# CYM1A113.net
KiCad netlist of a schematic drawn in EAGLE
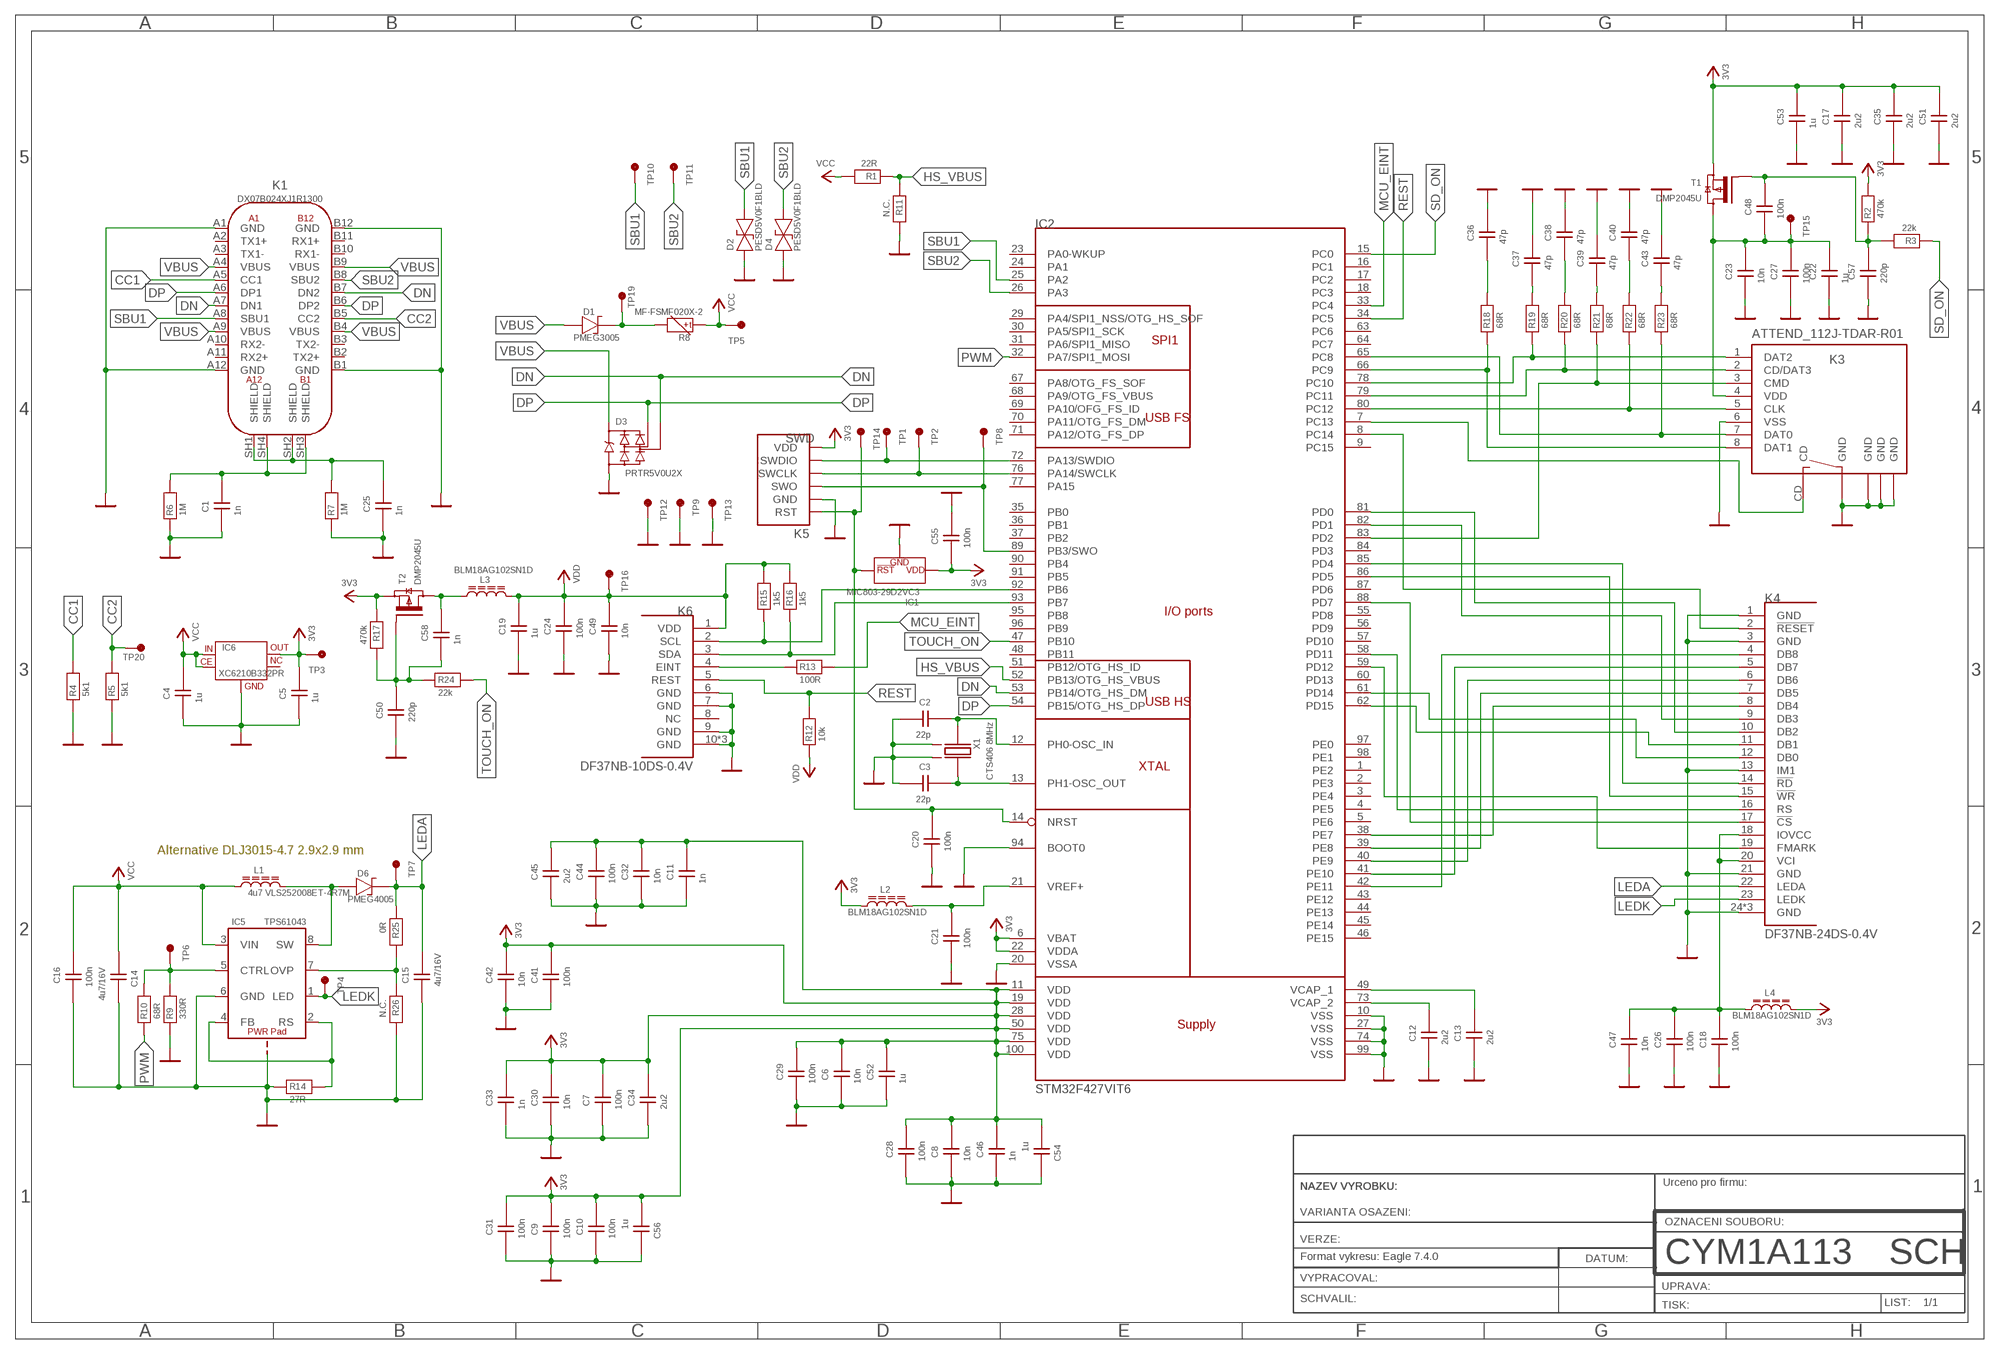
[diagram p0: schematic, sheet 1]

(export (version "E")
  (design (tool "Eeschema 10.0.6"))
  (components
    (comp (ref "C1")
      (value "1n")
      (footprint "eagle-import:0402")
      (libsource (lib "eagle-import") (part "C_0402"))
    )
    (comp (ref "C2")
      (value "22p")
      (footprint "eagle-import:0402")
      (libsource (lib "eagle-import") (part "C_0402"))
    )
    (comp (ref "C3")
      (value "22p")
      (footprint "eagle-import:0402")
      (libsource (lib "eagle-import") (part "C_0402"))
    )
    (comp (ref "C4")
      (value "1u")
      (footprint "eagle-import:0603_REFLOW")
      (libsource (lib "eagle-import") (part "C_0603$REFLOW"))
    )
    (comp (ref "C5")
      (value "1u")
      (footprint "eagle-import:0603")
      (libsource (lib "eagle-import") (part "C_0603"))
    )
    (comp (ref "C6")
      (value "10n")
      (footprint "eagle-import:0402")
      (libsource (lib "eagle-import") (part "C_0402"))
    )
    (comp (ref "C7")
      (value "100n")
      (footprint "eagle-import:0402")
      (libsource (lib "eagle-import") (part "C_0402"))
    )
    (comp (ref "C8")
      (value "10n")
      (footprint "eagle-import:0402")
      (libsource (lib "eagle-import") (part "C_0402"))
    )
    (comp (ref "C9")
      (value "100n")
      (footprint "eagle-import:0402")
      (libsource (lib "eagle-import") (part "C_0402"))
    )
    (comp (ref "C10")
      (value "100n")
      (footprint "eagle-import:0402")
      (libsource (lib "eagle-import") (part "C_0402"))
    )
    (comp (ref "C11")
      (value "1n")
      (footprint "eagle-import:0402")
      (libsource (lib "eagle-import") (part "C_0402"))
    )
    (comp (ref "C12")
      (value "2u2")
      (footprint "eagle-import:0805_REFLOW")
      (libsource (lib "eagle-import") (part "C_0805$REFLOW"))
    )
    (comp (ref "C13")
      (value "2u2")
      (footprint "eagle-import:0805_REFLOW")
      (libsource (lib "eagle-import") (part "C_0805$REFLOW"))
    )
    (comp (ref "C14")
      (value "4u7/16V")
      (footprint "eagle-import:0805_REFLOW")
      (libsource (lib "eagle-import") (part "C_0805$REFLOW"))
    )
    (comp (ref "C15")
      (value "4u7/16V")
      (footprint "eagle-import:0805_REFLOW")
      (libsource (lib "eagle-import") (part "C_0805$REFLOW"))
    )
    (comp (ref "C16")
      (value "100n")
      (footprint "eagle-import:0402")
      (libsource (lib "eagle-import") (part "C_0402"))
    )
    (comp (ref "C17")
      (value "2u2")
      (footprint "eagle-import:0805_REFLOW")
      (libsource (lib "eagle-import") (part "C_0805$REFLOW"))
    )
    (comp (ref "C18")
      (value "100n")
      (footprint "eagle-import:0402")
      (libsource (lib "eagle-import") (part "C_0402"))
    )
    (comp (ref "C19")
      (value "1u")
      (footprint "eagle-import:0603_REFLOW")
      (libsource (lib "eagle-import") (part "C_0603$REFLOW"))
    )
    (comp (ref "C20")
      (value "100n")
      (footprint "eagle-import:0402")
      (libsource (lib "eagle-import") (part "C_0402"))
    )
    (comp (ref "C21")
      (value "100n")
      (footprint "eagle-import:0402")
      (libsource (lib "eagle-import") (part "C_0402"))
    )
    (comp (ref "C22")
      (value "1u")
      (footprint "eagle-import:0603_REFLOW")
      (libsource (lib "eagle-import") (part "C_0603$REFLOW"))
    )
    (comp (ref "C23")
      (value "10n")
      (footprint "eagle-import:0402")
      (libsource (lib "eagle-import") (part "C_0402"))
    )
    (comp (ref "C24")
      (value "100n")
      (footprint "eagle-import:0402")
      (libsource (lib "eagle-import") (part "C_0402"))
    )
    (comp (ref "C25")
      (value "1n")
      (footprint "eagle-import:0402")
      (libsource (lib "eagle-import") (part "C_0402"))
    )
    (comp (ref "C26")
      (value "100n")
      (footprint "eagle-import:0402")
      (libsource (lib "eagle-import") (part "C_0402"))
    )
    (comp (ref "C27")
      (value "100n")
      (footprint "eagle-import:0402")
      (libsource (lib "eagle-import") (part "C_0402"))
    )
    (comp (ref "C28")
      (value "100n")
      (footprint "eagle-import:0402")
      (libsource (lib "eagle-import") (part "C_0402"))
    )
    (comp (ref "C29")
      (value "100n")
      (footprint "eagle-import:0402")
      (libsource (lib "eagle-import") (part "C_0402"))
    )
    (comp (ref "C30")
      (value "10n")
      (footprint "eagle-import:0402")
      (libsource (lib "eagle-import") (part "C_0402"))
    )
    (comp (ref "C31")
      (value "100n")
      (footprint "eagle-import:0402")
      (libsource (lib "eagle-import") (part "C_0402"))
    )
    (comp (ref "C32")
      (value "10n")
      (footprint "eagle-import:0402")
      (libsource (lib "eagle-import") (part "C_0402"))
    )
    (comp (ref "C33")
      (value "1n")
      (footprint "eagle-import:0402")
      (libsource (lib "eagle-import") (part "C_0402"))
    )
    (comp (ref "C34")
      (value "2u2")
      (footprint "eagle-import:0805_REFLOW")
      (libsource (lib "eagle-import") (part "C_0805$REFLOW"))
    )
    (comp (ref "C35")
      (value "2u2")
      (footprint "eagle-import:0805_REFLOW")
      (libsource (lib "eagle-import") (part "C_0805$REFLOW"))
    )
    (comp (ref "C36")
      (value "47p")
      (footprint "eagle-import:0402")
      (libsource (lib "eagle-import") (part "C_0402"))
    )
    (comp (ref "C37")
      (value "47p")
      (footprint "eagle-import:0402")
      (libsource (lib "eagle-import") (part "C_0402"))
    )
    (comp (ref "C38")
      (value "47p")
      (footprint "eagle-import:0402")
      (libsource (lib "eagle-import") (part "C_0402"))
    )
    (comp (ref "C39")
      (value "47p")
      (footprint "eagle-import:0402")
      (libsource (lib "eagle-import") (part "C_0402"))
    )
    (comp (ref "C40")
      (value "47p")
      (footprint "eagle-import:0402")
      (libsource (lib "eagle-import") (part "C_0402"))
    )
    (comp (ref "C41")
      (value "100n")
      (footprint "eagle-import:0402")
      (libsource (lib "eagle-import") (part "C_0402"))
    )
    (comp (ref "C42")
      (value "10n")
      (footprint "eagle-import:0402")
      (libsource (lib "eagle-import") (part "C_0402"))
    )
    (comp (ref "C43")
      (value "47p")
      (footprint "eagle-import:0402")
      (libsource (lib "eagle-import") (part "C_0402"))
    )
    (comp (ref "C44")
      (value "100n")
      (footprint "eagle-import:0402")
      (libsource (lib "eagle-import") (part "C_0402"))
    )
    (comp (ref "C45")
      (value "2u2")
      (footprint "eagle-import:0805_REFLOW")
      (libsource (lib "eagle-import") (part "C_0805$REFLOW"))
    )
    (comp (ref "C46")
      (value "1n")
      (footprint "eagle-import:0402")
      (libsource (lib "eagle-import") (part "C_0402"))
    )
    (comp (ref "C47")
      (value "10n")
      (footprint "eagle-import:0402")
      (libsource (lib "eagle-import") (part "C_0402"))
    )
    (comp (ref "C48")
      (value "100n")
      (footprint "eagle-import:0402")
      (libsource (lib "eagle-import") (part "C_0402"))
    )
    (comp (ref "C49")
      (value "10n")
      (footprint "eagle-import:0402")
      (libsource (lib "eagle-import") (part "C_0402"))
    )
    (comp (ref "C50")
      (value "220p")
      (footprint "eagle-import:0402")
      (libsource (lib "eagle-import") (part "C_0402"))
    )
    (comp (ref "C51")
      (value "2u2")
      (footprint "eagle-import:0805_REFLOW")
      (libsource (lib "eagle-import") (part "C_0805$REFLOW"))
    )
    (comp (ref "C52")
      (value "1u")
      (footprint "eagle-import:0603_REFLOW")
      (libsource (lib "eagle-import") (part "C_0603$REFLOW"))
    )
    (comp (ref "C53")
      (value "1u")
      (footprint "eagle-import:0603_REFLOW")
      (libsource (lib "eagle-import") (part "C_0603$REFLOW"))
    )
    (comp (ref "C54")
      (value "1u")
      (footprint "eagle-import:0603_REFLOW")
      (libsource (lib "eagle-import") (part "C_0603$REFLOW"))
    )
    (comp (ref "C55")
      (value "100n")
      (footprint "eagle-import:0402")
      (libsource (lib "eagle-import") (part "C_0402"))
    )
    (comp (ref "C56")
      (value "1u")
      (footprint "eagle-import:0603_REFLOW")
      (libsource (lib "eagle-import") (part "C_0603$REFLOW"))
    )
    (comp (ref "C57")
      (value "220p")
      (footprint "eagle-import:0402")
      (libsource (lib "eagle-import") (part "C_0402"))
    )
    (comp (ref "C58")
      (value "1n")
      (footprint "eagle-import:0402")
      (libsource (lib "eagle-import") (part "C_0402"))
    )
    (comp (ref "D1")
      (value "PMEG3005")
      (footprint "eagle-import:SOD323F")
      (libsource (lib "eagle-import") (part "DS_SOD323F"))
    )
    (comp (ref "D2")
      (value "PESD5V0F1BLD")
      (footprint "eagle-import:SOD882D")
      (libsource (lib "eagle-import") (part "D_TRANSIL_BI_SOD882D"))
    )
    (comp (ref "D3")
      (value "PRTR5V0U2X")
      (footprint "eagle-import:SOT143B_REFLOW")
      (libsource (lib "eagle-import") (part "PRTR5V0_SOT143B$REFLOW"))
    )
    (comp (ref "D4")
      (value "PESD5V0F1BLD")
      (footprint "eagle-import:SOD882D")
      (libsource (lib "eagle-import") (part "D_TRANSIL_BI_SOD882D"))
    )
    (comp (ref "D6")
      (value "PMEG4005")
      (footprint "eagle-import:SOD323F")
      (libsource (lib "eagle-import") (part "DS_SOD323F"))
    )
    (comp (ref "IC1")
      (value "MIC803-29D2VC3")
      (footprint "eagle-import:SOT23_MEDIUM_SIZE")
      (libsource (lib "eagle-import") (part "MIC803"))
    )
    (comp (ref "IC2")
      (value "STM32F427VIT6")
      (footprint "eagle-import:LQFP100_NO_CENTER_NO_TDOCU")
      (libsource (lib "eagle-import") (part "STM32F427_LQFP100"))
    )
    (comp (ref "IC5")
      (value "TPS61043")
      (footprint "eagle-import:WSON-8_3X3MM")
      (libsource (lib "eagle-import") (part "TP6104X_WSON-8_3X3MM"))
    )
    (comp (ref "IC6")
      (value "XC6210B332PR")
      (footprint "eagle-import:SOT89-5")
      (libsource (lib "eagle-import") (part "XC6210B_SOT89-5"))
    )
    (comp (ref "K1")
      (value "DX07B024XJ1R1300")
      (footprint "eagle-import:USB_C_JAE_DX07B024XJ1")
      (libsource (lib "eagle-import") (part "USB-C_JAE_DX07B024XJ1"))
    )
    (comp (ref "K3")
      (value "ATTEND_112J-TDAR-R01")
      (footprint "eagle-import:ATTEND_112J-TXAR-R01_SMALL")
      (libsource (lib "eagle-import") (part "KON_µSD_CARD_ATTEND_112J_TXAR_R01_SMALL"))
    )
    (comp (ref "K4")
      (value "DF37NB-24DS-0.4V")
      (footprint "eagle-import:DF37NB-24DS-0.4V")
      (libsource (lib "eagle-import") (part "DISPLEJ_154A2411CTP01"))
    )
    (comp (ref "K5")
      (value "SWD")
      (footprint "eagle-import:SWD")
      (libsource (lib "eagle-import") (part "SWD"))
    )
    (comp (ref "K6")
      (value "DF37NB-10DS-0.4V")
      (footprint "eagle-import:DF37NB-10DS-0.4V")
      (libsource (lib "eagle-import") (part "DISPLEJ_154A2411CTP01_TOUCH"))
    )
    (comp (ref "L1")
      (value "4u7 VLS252008ET-4R7M")
      (footprint "eagle-import:L_2.5X2.0")
      (libsource (lib "eagle-import") (part "L_2.5X2.0"))
    )
    (comp (ref "L2")
      (value "BLM18AG102SN1D")
      (footprint "eagle-import:0603_REFLOW")
      (libsource (lib "eagle-import") (part "L_0603$REFLOW"))
    )
    (comp (ref "L3")
      (value "BLM18AG102SN1D")
      (footprint "eagle-import:0603_REFLOW")
      (libsource (lib "eagle-import") (part "L_0603$REFLOW"))
    )
    (comp (ref "L4")
      (value "BLM18AG102SN1D")
      (footprint "eagle-import:0603_REFLOW")
      (libsource (lib "eagle-import") (part "L_0603$REFLOW"))
    )
    (comp (ref "R1")
      (value "22R")
      (footprint "eagle-import:0402")
      (libsource (lib "eagle-import") (part "R_0402"))
    )
    (comp (ref "R2")
      (value "470k")
      (footprint "eagle-import:0402")
      (libsource (lib "eagle-import") (part "R_0402"))
    )
    (comp (ref "R3")
      (value "22k")
      (footprint "eagle-import:0402")
      (libsource (lib "eagle-import") (part "R_0402"))
    )
    (comp (ref "R4")
      (value "5k1")
      (footprint "eagle-import:0402")
      (libsource (lib "eagle-import") (part "R_0402"))
    )
    (comp (ref "R5")
      (value "5k1")
      (footprint "eagle-import:0402")
      (libsource (lib "eagle-import") (part "R_0402"))
    )
    (comp (ref "R6")
      (value "1M")
      (footprint "eagle-import:0402")
      (libsource (lib "eagle-import") (part "R_0402"))
    )
    (comp (ref "R7")
      (value "1M")
      (footprint "eagle-import:0402")
      (libsource (lib "eagle-import") (part "R_0402"))
    )
    (comp (ref "R8")
      (value "MF-FSMF020X-2")
      (footprint "eagle-import:0603")
      (libsource (lib "eagle-import") (part "POLYSWITCH_0603"))
    )
    (comp (ref "R9")
      (value "330R")
      (footprint "eagle-import:0402")
      (libsource (lib "eagle-import") (part "R_0402"))
    )
    (comp (ref "R10")
      (value "68R")
      (footprint "eagle-import:0402")
      (libsource (lib "eagle-import") (part "R_0402"))
    )
    (comp (ref "R11")
      (value "N.C.")
      (footprint "eagle-import:0402")
      (libsource (lib "eagle-import") (part "R_0402"))
    )
    (comp (ref "R12")
      (value "10k")
      (footprint "eagle-import:0402")
      (libsource (lib "eagle-import") (part "R_0402"))
    )
    (comp (ref "R13")
      (value "100R")
      (footprint "eagle-import:0402")
      (libsource (lib "eagle-import") (part "R_0402"))
    )
    (comp (ref "R14")
      (value "27R")
      (footprint "eagle-import:0402")
      (libsource (lib "eagle-import") (part "R_0402"))
    )
    (comp (ref "R15")
      (value "1k5")
      (footprint "eagle-import:0402")
      (libsource (lib "eagle-import") (part "R_0402"))
    )
    (comp (ref "R16")
      (value "1k5")
      (footprint "eagle-import:0402")
      (libsource (lib "eagle-import") (part "R_0402"))
    )
    (comp (ref "R17")
      (value "470k")
      (footprint "eagle-import:0402")
      (libsource (lib "eagle-import") (part "R_0402"))
    )
    (comp (ref "R18")
      (value "68R")
      (footprint "eagle-import:0402")
      (libsource (lib "eagle-import") (part "R_0402"))
    )
    (comp (ref "R19")
      (value "68R")
      (footprint "eagle-import:0402")
      (libsource (lib "eagle-import") (part "R_0402"))
    )
    (comp (ref "R20")
      (value "68R")
      (footprint "eagle-import:0402")
      (libsource (lib "eagle-import") (part "R_0402"))
    )
    (comp (ref "R21")
      (value "68R")
      (footprint "eagle-import:0402")
      (libsource (lib "eagle-import") (part "R_0402"))
    )
    (comp (ref "R22")
      (value "68R")
      (footprint "eagle-import:0402")
      (libsource (lib "eagle-import") (part "R_0402"))
    )
    (comp (ref "R23")
      (value "68R")
      (footprint "eagle-import:0402")
      (libsource (lib "eagle-import") (part "R_0402"))
    )
    (comp (ref "R24")
      (value "22k")
      (footprint "eagle-import:0402")
      (libsource (lib "eagle-import") (part "R_0402"))
    )
    (comp (ref "R25")
      (value "0R")
      (footprint "eagle-import:0402")
      (libsource (lib "eagle-import") (part "R_0402"))
    )
    (comp (ref "R26")
      (value "N.C.")
      (footprint "eagle-import:0402")
      (libsource (lib "eagle-import") (part "R_0402"))
    )
    (comp (ref "T1")
      (value "DMP2045U")
      (footprint "eagle-import:SOT23_REFLOW")
      (libsource (lib "eagle-import") (part "PMOS_SOT-23_REF"))
    )
    (comp (ref "T2")
      (value "DMP2045U")
      (footprint "eagle-import:SOT23_REFLOW")
      (libsource (lib "eagle-import") (part "PMOS_SOT-23_REF"))
    )
    (comp (ref "TP1")
      (value "MB_1.27")
      (footprint "eagle-import:MB1.27")
      (libsource (lib "eagle-import") (part "MB_1.27"))
    )
    (comp (ref "TP2")
      (value "MB_1.27")
      (footprint "eagle-import:MB1.27")
      (libsource (lib "eagle-import") (part "MB_1.27"))
    )
    (comp (ref "TP3")
      (value "MB_1.50")
      (footprint "eagle-import:MB1.5")
      (libsource (lib "eagle-import") (part "MB_1.50"))
    )
    (comp (ref "TP4")
      (value "MB_1.27")
      (footprint "eagle-import:MB1.27")
      (libsource (lib "eagle-import") (part "MB_1.27"))
    )
    (comp (ref "TP5")
      (value "MB_1.50")
      (footprint "eagle-import:MB1.5")
      (libsource (lib "eagle-import") (part "MB_1.50"))
    )
    (comp (ref "TP6")
      (value "MB_1.27")
      (footprint "eagle-import:MB1.27")
      (libsource (lib "eagle-import") (part "MB_1.27"))
    )
    (comp (ref "TP7")
      (value "MB_1.27")
      (footprint "eagle-import:MB1.27")
      (libsource (lib "eagle-import") (part "MB_1.27"))
    )
    (comp (ref "TP8")
      (value "MB_1.27")
      (footprint "eagle-import:MB1.27")
      (libsource (lib "eagle-import") (part "MB_1.27"))
    )
    (comp (ref "TP9")
      (value "MB_1.27")
      (footprint "eagle-import:MB1.27")
      (libsource (lib "eagle-import") (part "MB_1.27"))
    )
    (comp (ref "TP10")
      (value "MB_1.50")
      (footprint "eagle-import:MB1.5")
      (libsource (lib "eagle-import") (part "MB_1.50"))
    )
    (comp (ref "TP11")
      (value "MB_1.50")
      (footprint "eagle-import:MB1.5")
      (libsource (lib "eagle-import") (part "MB_1.50"))
    )
    (comp (ref "TP12")
      (value "MB_1.27")
      (footprint "eagle-import:MB1.27")
      (libsource (lib "eagle-import") (part "MB_1.27"))
    )
    (comp (ref "TP13")
      (value "MB_1.27")
      (footprint "eagle-import:MB1.27")
      (libsource (lib "eagle-import") (part "MB_1.27"))
    )
    (comp (ref "TP14")
      (value "MB_1.27")
      (footprint "eagle-import:MB1.27")
      (libsource (lib "eagle-import") (part "MB_1.27"))
    )
    (comp (ref "TP15")
      (value "MB_1.27")
      (footprint "eagle-import:MB1.27")
      (libsource (lib "eagle-import") (part "MB_1.27"))
    )
    (comp (ref "TP16")
      (value "MB_1.27")
      (footprint "eagle-import:MB1.27")
      (libsource (lib "eagle-import") (part "MB_1.27"))
    )
    (comp (ref "TP19")
      (value "MB_1.00")
      (footprint "eagle-import:MB_1.00")
      (libsource (lib "eagle-import") (part "MB_1.00"))
    )
    (comp (ref "TP20")
      (value "MB_1.00")
      (footprint "eagle-import:MB_1.00")
      (libsource (lib "eagle-import") (part "MB_1.00"))
    )
    (comp (ref "X1")
      (value "CTS406 8MHz")
      (footprint "eagle-import:X6,0X3,5")
      (libsource (lib "eagle-import") (part "X_4V_6,0X3,5"))
    )
  )
  (nets
    (net (code "1") (name "3V3") (class "Default")
      (node (ref "C10") (pin "P$2") (pinfunction "2_P$2") (pintype "passive"))
      (node (ref "C11") (pin "P$2") (pinfunction "2_P$2") (pintype "passive"))
      (node (ref "C17") (pin "2") (pinfunction "2_2") (pintype "passive"))
      (node (ref "C28") (pin "P$2") (pinfunction "2_P$2") (pintype "passive"))
      (node (ref "C29") (pin "P$2") (pinfunction "2_P$2") (pintype "passive"))
      (node (ref "C30") (pin "P$2") (pinfunction "2_P$2") (pintype "passive"))
      (node (ref "C31") (pin "P$2") (pinfunction "2_P$2") (pintype "passive"))
      (node (ref "C32") (pin "P$2") (pinfunction "2_P$2") (pintype "passive"))
      (node (ref "C33") (pin "P$2") (pinfunction "2_P$2") (pintype "passive"))
      (node (ref "C34") (pin "2") (pinfunction "2_2") (pintype "passive"))
      (node (ref "C35") (pin "2") (pinfunction "2_2") (pintype "passive"))
      (node (ref "C41") (pin "P$2") (pinfunction "2_P$2") (pintype "passive"))
      (node (ref "C42") (pin "P$2") (pinfunction "2_P$2") (pintype "passive"))
      (node (ref "C44") (pin "P$2") (pinfunction "2_P$2") (pintype "passive"))
      (node (ref "C45") (pin "2") (pinfunction "2_2") (pintype "passive"))
      (node (ref "C46") (pin "P$2") (pinfunction "2_P$2") (pintype "passive"))
      (node (ref "C5") (pin "2") (pinfunction "2_2") (pintype "passive"))
      (node (ref "C51") (pin "2") (pinfunction "2_2") (pintype "passive"))
      (node (ref "C52") (pin "2") (pinfunction "2_2") (pintype "passive"))
      (node (ref "C53") (pin "2") (pinfunction "2_2") (pintype "passive"))
      (node (ref "C54") (pin "1") (pinfunction "1_1") (pintype "passive"))
      (node (ref "C55") (pin "P$1") (pinfunction "1_P$1") (pintype "passive"))
      (node (ref "C56") (pin "1") (pinfunction "1_1") (pintype "passive"))
      (node (ref "C6") (pin "P$2") (pinfunction "2_P$2") (pintype "passive"))
      (node (ref "C7") (pin "P$2") (pinfunction "2_P$2") (pintype "passive"))
      (node (ref "C8") (pin "P$2") (pinfunction "2_P$2") (pintype "passive"))
      (node (ref "C9") (pin "P$2") (pinfunction "2_P$2") (pintype "passive"))
      (node (ref "IC1") (pin "3") (pinfunction "VDD_3") (pintype "passive"))
      (node (ref "IC2") (pin "100") (pinfunction "VDD_100") (pintype "power_in"))
      (node (ref "IC2") (pin "11") (pinfunction "VDD_11") (pintype "power_in"))
      (node (ref "IC2") (pin "19") (pinfunction "VDD_19") (pintype "power_in"))
      (node (ref "IC2") (pin "22") (pinfunction "VDDA_22") (pintype "power_in"))
      (node (ref "IC2") (pin "28") (pinfunction "VDD_28") (pintype "power_in"))
      (node (ref "IC2") (pin "50") (pinfunction "VDD_50") (pintype "power_in"))
      (node (ref "IC2") (pin "6") (pinfunction "VBAT_6") (pintype "power_in"))
      (node (ref "IC2") (pin "75") (pinfunction "VDD_75") (pintype "power_in"))
      (node (ref "IC6") (pin "5") (pinfunction "OUT_5") (pintype "passive"))
      (node (ref "K5") (pin "VCC") (pinfunction "VDD_VCC") (pintype "passive"))
      (node (ref "L2") (pin "1") (pinfunction "1_1") (pintype "passive"))
      (node (ref "L4") (pin "2") (pinfunction "2_2") (pintype "passive"))
      (node (ref "R17") (pin "P$1") (pinfunction "1_P$1") (pintype "passive"))
      (node (ref "R2") (pin "P$2") (pinfunction "2_P$2") (pintype "passive"))
      (node (ref "T1") (pin "1") (pinfunction "S_1") (pintype "passive"))
      (node (ref "T2") (pin "1") (pinfunction "S_1") (pintype "passive"))
      (node (ref "TP3") (pin "1") (pinfunction "1_1") (pintype "passive"))
    )
    (net (code "2") (name "CC1") (class "Default")
      (node (ref "K1") (pin "A5") (pinfunction "CC1_A5") (pintype "passive"))
      (node (ref "R4") (pin "P$2") (pinfunction "2_P$2") (pintype "passive"))
    )
    (net (code "3") (name "CC2") (class "Default")
      (node (ref "K1") (pin "B5") (pinfunction "CC2_B5") (pintype "passive"))
      (node (ref "R5") (pin "P$2") (pinfunction "2_P$2") (pintype "passive"))
      (node (ref "TP20") (pin "1") (pinfunction "1_1") (pintype "passive"))
    )
    (net (code "4") (name "DN") (class "Default")
      (node (ref "D3") (pin "3") (pinfunction "I/O2_3") (pintype "passive"))
      (node (ref "IC2") (pin "53") (pinfunction "PB14/OTG_HS_DM_53") (pintype "bidirectional"))
      (node (ref "K1") (pin "A7") (pinfunction "DN1_A7") (pintype "passive"))
      (node (ref "K1") (pin "B7") (pinfunction "DN2_B7") (pintype "passive"))
    )
    (net (code "5") (name "DP") (class "Default")
      (node (ref "D3") (pin "2") (pinfunction "I/O1_2") (pintype "passive"))
      (node (ref "IC2") (pin "54") (pinfunction "PB15/OTG_HS_DP_54") (pintype "bidirectional"))
      (node (ref "K1") (pin "A6") (pinfunction "DP1_A6") (pintype "passive"))
      (node (ref "K1") (pin "B6") (pinfunction "DP2_B6") (pintype "passive"))
    )
    (net (code "6") (name "GND") (class "Default")
      (node (ref "C1") (pin "P$1") (pinfunction "1_P$1") (pintype "passive"))
      (node (ref "C10") (pin "P$1") (pinfunction "1_P$1") (pintype "passive"))
      (node (ref "C11") (pin "P$1") (pinfunction "1_P$1") (pintype "passive"))
      (node (ref "C12") (pin "1") (pinfunction "1_1") (pintype "passive"))
      (node (ref "C13") (pin "1") (pinfunction "1_1") (pintype "passive"))
      (node (ref "C14") (pin "2") (pinfunction "2_2") (pintype "passive"))
      (node (ref "C15") (pin "1") (pinfunction "1_1") (pintype "passive"))
      (node (ref "C16") (pin "P$1") (pinfunction "1_P$1") (pintype "passive"))
      (node (ref "C17") (pin "1") (pinfunction "1_1") (pintype "passive"))
      (node (ref "C18") (pin "P$1") (pinfunction "1_P$1") (pintype "passive"))
      (node (ref "C19") (pin "1") (pinfunction "1_1") (pintype "passive"))
      (node (ref "C2") (pin "P$1") (pinfunction "1_P$1") (pintype "passive"))
      (node (ref "C20") (pin "P$1") (pinfunction "1_P$1") (pintype "passive"))
      (node (ref "C21") (pin "P$1") (pinfunction "1_P$1") (pintype "passive"))
      (node (ref "C22") (pin "1") (pinfunction "1_1") (pintype "passive"))
      (node (ref "C23") (pin "P$1") (pinfunction "1_P$1") (pintype "passive"))
      (node (ref "C24") (pin "P$1") (pinfunction "1_P$1") (pintype "passive"))
      (node (ref "C25") (pin "P$1") (pinfunction "1_P$1") (pintype "passive"))
      (node (ref "C26") (pin "P$1") (pinfunction "1_P$1") (pintype "passive"))
      (node (ref "C27") (pin "P$1") (pinfunction "1_P$1") (pintype "passive"))
      (node (ref "C28") (pin "P$1") (pinfunction "1_P$1") (pintype "passive"))
      (node (ref "C29") (pin "P$1") (pinfunction "1_P$1") (pintype "passive"))
      (node (ref "C3") (pin "P$1") (pinfunction "1_P$1") (pintype "passive"))
      (node (ref "C30") (pin "P$1") (pinfunction "1_P$1") (pintype "passive"))
      (node (ref "C31") (pin "P$1") (pinfunction "1_P$1") (pintype "passive"))
      (node (ref "C32") (pin "P$1") (pinfunction "1_P$1") (pintype "passive"))
      (node (ref "C33") (pin "P$1") (pinfunction "1_P$1") (pintype "passive"))
      (node (ref "C34") (pin "1") (pinfunction "1_1") (pintype "passive"))
      (node (ref "C35") (pin "1") (pinfunction "1_1") (pintype "passive"))
      (node (ref "C36") (pin "P$2") (pinfunction "2_P$2") (pintype "passive"))
      (node (ref "C37") (pin "P$2") (pinfunction "2_P$2") (pintype "passive"))
      (node (ref "C38") (pin "P$2") (pinfunction "2_P$2") (pintype "passive"))
      (node (ref "C39") (pin "P$2") (pinfunction "2_P$2") (pintype "passive"))
      (node (ref "C4") (pin "1") (pinfunction "1_1") (pintype "passive"))
      (node (ref "C40") (pin "P$2") (pinfunction "2_P$2") (pintype "passive"))
      (node (ref "C41") (pin "P$1") (pinfunction "1_P$1") (pintype "passive"))
      (node (ref "C42") (pin "P$1") (pinfunction "1_P$1") (pintype "passive"))
      (node (ref "C43") (pin "P$2") (pinfunction "2_P$2") (pintype "passive"))
      (node (ref "C44") (pin "P$1") (pinfunction "1_P$1") (pintype "passive"))
      (node (ref "C45") (pin "1") (pinfunction "1_1") (pintype "passive"))
      (node (ref "C46") (pin "P$1") (pinfunction "1_P$1") (pintype "passive"))
      (node (ref "C47") (pin "P$1") (pinfunction "1_P$1") (pintype "passive"))
      (node (ref "C49") (pin "P$1") (pinfunction "1_P$1") (pintype "passive"))
      (node (ref "C5") (pin "1") (pinfunction "1_1") (pintype "passive"))
      (node (ref "C50") (pin "P$1") (pinfunction "1_P$1") (pintype "passive"))
      (node (ref "C51") (pin "1") (pinfunction "1_1") (pintype "passive"))
      (node (ref "C52") (pin "1") (pinfunction "1_1") (pintype "passive"))
      (node (ref "C53") (pin "1") (pinfunction "1_1") (pintype "passive"))
      (node (ref "C54") (pin "2") (pinfunction "2_2") (pintype "passive"))
      (node (ref "C55") (pin "P$2") (pinfunction "2_P$2") (pintype "passive"))
      (node (ref "C56") (pin "2") (pinfunction "2_2") (pintype "passive"))
      (node (ref "C57") (pin "P$1") (pinfunction "1_P$1") (pintype "passive"))
      (node (ref "C6") (pin "P$1") (pinfunction "1_P$1") (pintype "passive"))
      (node (ref "C7") (pin "P$1") (pinfunction "1_P$1") (pintype "passive"))
      (node (ref "C8") (pin "P$1") (pinfunction "1_P$1") (pintype "passive"))
      (node (ref "C9") (pin "P$1") (pinfunction "1_P$1") (pintype "passive"))
      (node (ref "D2") (pin "1") (pinfunction "1_1") (pintype "passive"))
      (node (ref "D3") (pin "1") (pinfunction "GND_1") (pintype "passive"))
      (node (ref "D4") (pin "1") (pinfunction "1_1") (pintype "passive"))
      (node (ref "IC1") (pin "1") (pinfunction "GND_1") (pintype "passive"))
      (node (ref "IC2") (pin "10") (pinfunction "VSS_10") (pintype "power_in"))
      (node (ref "IC2") (pin "20") (pinfunction "VSSA_20") (pintype "power_in"))
      (node (ref "IC2") (pin "27") (pinfunction "VSS_27") (pintype "power_in"))
      (node (ref "IC2") (pin "74") (pinfunction "VSS_74") (pintype "power_in"))
      (node (ref "IC2") (pin "94") (pinfunction "BOOT0_94") (pintype "input"))
      (node (ref "IC2") (pin "99") (pinfunction "VSS_99") (pintype "power_in"))
      (node (ref "IC5") (pin "6") (pinfunction "GND_6") (pintype "power_in"))
      (node (ref "IC5") (pin "EP") (pinfunction "EP_EP") (pintype "passive"))
      (node (ref "IC5") (pin "EP$1") (pinfunction "EP_EP$1") (pintype "passive"))
      (node (ref "IC5") (pin "EP$2") (pinfunction "EP_EP$2") (pintype "passive"))
      (node (ref "IC5") (pin "EP$3") (pinfunction "EP_EP$3") (pintype "passive"))
      (node (ref "IC5") (pin "EP$4") (pinfunction "EP_EP$4") (pintype "passive"))
      (node (ref "IC6") (pin "2") (pinfunction "GND_2") (pintype "passive"))
      (node (ref "K1") (pin "A1") (pinfunction "GND_A1") (pintype "passive"))
      (node (ref "K1") (pin "A12") (pinfunction "GND_A12") (pintype "passive"))
      (node (ref "K1") (pin "B1") (pinfunction "GND_B1") (pintype "passive"))
      (node (ref "K1") (pin "B12") (pinfunction "GND_B12") (pintype "passive"))
      (node (ref "K3") (pin "6") (pinfunction "VSS_6") (pintype "bidirectional"))
      (node (ref "K3") (pin "GND@1") (pinfunction "GND_GND@1") (pintype "power_in"))
      (node (ref "K3") (pin "GND@2") (pinfunction "GND_GND@2") (pintype "power_in"))
      (node (ref "K3") (pin "GND@3") (pinfunction "GND_GND@3") (pintype "power_in"))
      (node (ref "K3") (pin "GND@4") (pinfunction "GND_GND@4") (pintype "power_in"))
      (node (ref "K4") (pin "1") (pinfunction "GND_1") (pintype "power_in"))
      (node (ref "K4") (pin "13") (pinfunction "IM1_13") (pintype "bidirectional"))
      (node (ref "K4") (pin "21") (pinfunction "GND_21") (pintype "power_in"))
      (node (ref "K4") (pin "24") (pinfunction "GND_24") (pintype "power_in"))
      (node (ref "K4") (pin "25") (pinfunction "GND_25") (pintype "power_in"))
      (node (ref "K4") (pin "26") (pinfunction "GND_26") (pintype "power_in"))
      (node (ref "K4") (pin "3") (pinfunction "GND_3") (pintype "power_in"))
      (node (ref "K5") (pin "GND") (pinfunction "GND_GND") (pintype "passive"))
      (node (ref "K6") (pin "10") (pinfunction "GND_10") (pintype "power_in"))
      (node (ref "K6") (pin "11") (pinfunction "GND_11") (pintype "power_in"))
      (node (ref "K6") (pin "12") (pinfunction "GND_12") (pintype "power_in"))
      (node (ref "K6") (pin "6") (pinfunction "GND_6") (pintype "power_in"))
      (node (ref "K6") (pin "7") (pinfunction "GND_7") (pintype "power_in"))
      (node (ref "K6") (pin "9") (pinfunction "GND_9") (pintype "power_in"))
      (node (ref "R11") (pin "P$2") (pinfunction "2_P$2") (pintype "passive"))
      (node (ref "R14") (pin "P$1") (pinfunction "1_P$1") (pintype "passive"))
      (node (ref "R26") (pin "P$2") (pinfunction "2_P$2") (pintype "passive"))
      (node (ref "R4") (pin "P$1") (pinfunction "1_P$1") (pintype "passive"))
      (node (ref "R5") (pin "P$1") (pinfunction "1_P$1") (pintype "passive"))
      (node (ref "R6") (pin "P$1") (pinfunction "1_P$1") (pintype "passive"))
      (node (ref "R7") (pin "P$1") (pinfunction "1_P$1") (pintype "passive"))
      (node (ref "R9") (pin "P$1") (pinfunction "1_P$1") (pintype "passive"))
      (node (ref "TP12") (pin "1") (pinfunction "1_1") (pintype "passive"))
      (node (ref "TP13") (pin "1") (pinfunction "1_1") (pintype "passive"))
      (node (ref "TP9") (pin "1") (pinfunction "1_1") (pintype "passive"))
      (node (ref "X1") (pin "2") (pinfunction "GND1_2") (pintype "passive"))
      (node (ref "X1") (pin "4") (pinfunction "GND2_4") (pintype "passive"))
    )
    (net (code "7") (name "HS_VBUS") (class "Default")
      (node (ref "IC2") (pin "52") (pinfunction "PB13/OTG_HS_VBUS_52") (pintype "bidirectional"))
      (node (ref "R1") (pin "P$1") (pinfunction "1_P$1") (pintype "passive"))
      (node (ref "R11") (pin "P$1") (pinfunction "1_P$1") (pintype "passive"))
    )
    (net (code "8") (name "LEDA") (class "Default")
      (node (ref "C15") (pin "2") (pinfunction "2_2") (pintype "passive"))
      (node (ref "D6") (pin "K") (pinfunction "2_K") (pintype "passive"))
      (node (ref "K4") (pin "22") (pinfunction "LEDA_22") (pintype "passive"))
      (node (ref "R25") (pin "P$1") (pinfunction "1_P$1") (pintype "passive"))
      (node (ref "TP7") (pin "1") (pinfunction "1_1") (pintype "passive"))
    )
    (net (code "9") (name "LEDK") (class "Default")
      (node (ref "IC5") (pin "1") (pinfunction "LED_1") (pintype "passive"))
      (node (ref "K4") (pin "23") (pinfunction "LEDK_23") (pintype "passive"))
      (node (ref "TP4") (pin "1") (pinfunction "1_1") (pintype "passive"))
    )
    (net (code "10") (name "MCU_EINT") (class "Default")
      (node (ref "IC2") (pin "33") (pinfunction "PC4_33") (pintype "bidirectional"))
      (node (ref "R13") (pin "P$2") (pinfunction "2_P$2") (pintype "passive"))
    )
    (net (code "11") (name "Net-(C1-2)") (class "Default")
      (node (ref "C1") (pin "P$2") (pinfunction "2_P$2") (pintype "passive"))
      (node (ref "K1") (pin "SH3") (pinfunction "SHIELD_SH3") (pintype "passive"))
      (node (ref "K1") (pin "SH4") (pinfunction "SHIELD_SH4") (pintype "passive"))
      (node (ref "R6") (pin "P$2") (pinfunction "2_P$2") (pintype "passive"))
    )
    (net (code "12") (name "Net-(C2-2)") (class "Default")
      (node (ref "C2") (pin "P$2") (pinfunction "2_P$2") (pintype "passive"))
      (node (ref "IC2") (pin "12") (pinfunction "PH0-OSC_IN_12") (pintype "input"))
      (node (ref "X1") (pin "1") (pinfunction "1_1") (pintype "passive"))
    )
    (net (code "13") (name "Net-(C3-2)") (class "Default")
      (node (ref "C3") (pin "P$2") (pinfunction "2_P$2") (pintype "passive"))
      (node (ref "IC2") (pin "13") (pinfunction "PH1-OSC_OUT_13") (pintype "output"))
      (node (ref "X1") (pin "3") (pinfunction "2_3") (pintype "passive"))
    )
    (net (code "14") (name "Net-(C18-2)") (class "Default")
      (node (ref "C18") (pin "P$2") (pinfunction "2_P$2") (pintype "passive"))
      (node (ref "C26") (pin "P$2") (pinfunction "2_P$2") (pintype "passive"))
      (node (ref "C47") (pin "P$2") (pinfunction "2_P$2") (pintype "passive"))
      (node (ref "K4") (pin "18") (pinfunction "IOVCC_18") (pintype "power_in"))
      (node (ref "K4") (pin "20") (pinfunction "VCI_20") (pintype "passive"))
      (node (ref "L4") (pin "1") (pinfunction "1_1") (pintype "passive"))
    )
    (net (code "15") (name "Net-(C20-2)") (class "Default")
      (node (ref "C20") (pin "P$2") (pinfunction "2_P$2") (pintype "passive"))
      (node (ref "IC1") (pin "2") (pinfunction "RES_2") (pintype "passive"))
      (node (ref "IC2") (pin "14") (pinfunction "NRST_14") (pintype "bidirectional"))
      (node (ref "K5") (pin "RST") (pinfunction "RST_RST") (pintype "passive"))
      (node (ref "TP14") (pin "1") (pinfunction "1_1") (pintype "passive"))
    )
    (net (code "16") (name "Net-(C21-2)") (class "Default")
      (node (ref "C21") (pin "P$2") (pinfunction "2_P$2") (pintype "passive"))
      (node (ref "IC2") (pin "21") (pinfunction "VREF+_21") (pintype "power_in"))
      (node (ref "L2") (pin "2") (pinfunction "2_2") (pintype "passive"))
    )
    (net (code "17") (name "Net-(C23-2)") (class "Default")
      (node (ref "C22") (pin "2") (pinfunction "2_2") (pintype "passive"))
      (node (ref "C23") (pin "P$2") (pinfunction "2_P$2") (pintype "passive"))
      (node (ref "C27") (pin "P$2") (pinfunction "2_P$2") (pintype "passive"))
      (node (ref "C48") (pin "P$1") (pinfunction "1_P$1") (pintype "passive"))
      (node (ref "K3") (pin "4") (pinfunction "VDD_4") (pintype "power_in"))
      (node (ref "T1") (pin "3") (pinfunction "D_3") (pintype "passive"))
      (node (ref "TP15") (pin "1") (pinfunction "1_1") (pintype "passive"))
    )
    (net (code "18") (name "Net-(C25-2)") (class "Default")
      (node (ref "C25") (pin "P$2") (pinfunction "2_P$2") (pintype "passive"))
      (node (ref "K1") (pin "SH1") (pinfunction "SHIELD_SH1") (pintype "passive"))
      (node (ref "K1") (pin "SH2") (pinfunction "SHIELD_SH2") (pintype "passive"))
      (node (ref "R7") (pin "P$2") (pinfunction "2_P$2") (pintype "passive"))
    )
    (net (code "19") (name "Net-(C36-1)") (class "Default")
      (node (ref "C36") (pin "P$1") (pinfunction "1_P$1") (pintype "passive"))
      (node (ref "R18") (pin "P$2") (pinfunction "2_P$2") (pintype "passive"))
    )
    (net (code "20") (name "Net-(C37-1)") (class "Default")
      (node (ref "C37") (pin "P$1") (pinfunction "1_P$1") (pintype "passive"))
      (node (ref "R19") (pin "P$2") (pinfunction "2_P$2") (pintype "passive"))
    )
    (net (code "21") (name "Net-(C38-1)") (class "Default")
      (node (ref "C38") (pin "P$1") (pinfunction "1_P$1") (pintype "passive"))
      (node (ref "R20") (pin "P$2") (pinfunction "2_P$2") (pintype "passive"))
    )
    (net (code "22") (name "Net-(C39-1)") (class "Default")
      (node (ref "C39") (pin "P$1") (pinfunction "1_P$1") (pintype "passive"))
      (node (ref "R21") (pin "P$2") (pinfunction "2_P$2") (pintype "passive"))
    )
    (net (code "23") (name "Net-(C40-1)") (class "Default")
      (node (ref "C40") (pin "P$1") (pinfunction "1_P$1") (pintype "passive"))
      (node (ref "R22") (pin "P$2") (pinfunction "2_P$2") (pintype "passive"))
    )
    (net (code "24") (name "Net-(C43-1)") (class "Default")
      (node (ref "C43") (pin "P$1") (pinfunction "1_P$1") (pintype "passive"))
      (node (ref "R23") (pin "P$2") (pinfunction "2_P$2") (pintype "passive"))
    )
    (net (code "25") (name "Net-(C48-2)") (class "Default")
      (node (ref "C48") (pin "P$2") (pinfunction "2_P$2") (pintype "passive"))
      (node (ref "C57") (pin "P$2") (pinfunction "2_P$2") (pintype "passive"))
      (node (ref "R2") (pin "P$1") (pinfunction "1_P$1") (pintype "passive"))
      (node (ref "R3") (pin "P$2") (pinfunction "2_P$2") (pintype "passive"))
      (node (ref "T1") (pin "2") (pinfunction "G_2") (pintype "input"))
    )
    (net (code "26") (name "Net-(C50-2)") (class "Default")
      (node (ref "C50") (pin "P$2") (pinfunction "2_P$2") (pintype "passive"))
      (node (ref "C58") (pin "P$1") (pinfunction "1_P$1") (pintype "passive"))
      (node (ref "R17") (pin "P$2") (pinfunction "2_P$2") (pintype "passive"))
      (node (ref "R24") (pin "P$1") (pinfunction "1_P$1") (pintype "passive"))
      (node (ref "T2") (pin "2") (pinfunction "G_2") (pintype "input"))
    )
    (net (code "27") (name "Net-(C58-2)") (class "Default")
      (node (ref "C58") (pin "P$2") (pinfunction "2_P$2") (pintype "passive"))
      (node (ref "L3") (pin "1") (pinfunction "1_1") (pintype "passive"))
      (node (ref "T2") (pin "3") (pinfunction "D_3") (pintype "passive"))
    )
    (net (code "28") (name "Net-(D1-2)") (class "Default")
      (node (ref "D1") (pin "K") (pinfunction "2_K") (pintype "passive"))
      (node (ref "R8") (pin "2") (pinfunction "2_2") (pintype "passive"))
      (node (ref "TP19") (pin "1") (pinfunction "1_1") (pintype "passive"))
    )
    (net (code "29") (name "Net-(D6-1)") (class "Default")
      (node (ref "D6") (pin "A") (pinfunction "1_A") (pintype "passive"))
      (node (ref "IC5") (pin "8") (pinfunction "SW_8") (pintype "output"))
      (node (ref "L1") (pin "2") (pinfunction "2_2") (pintype "passive"))
    )
    (net (code "30") (name "Net-(IC2-PA13{slash}SWDIO)") (class "Default")
      (node (ref "IC2") (pin "72") (pinfunction "PA13/SWDIO_72") (pintype "bidirectional"))
      (node (ref "K5") (pin "SWDIO") (pinfunction "SWDIO_SWDIO") (pintype "passive"))
      (node (ref "TP1") (pin "1") (pinfunction "1_1") (pintype "passive"))
    )
    (net (code "31") (name "Net-(IC2-PA14{slash}SWCLK)") (class "Default")
      (node (ref "IC2") (pin "76") (pinfunction "PA14/SWCLK_76") (pintype "bidirectional"))
      (node (ref "K5") (pin "SWCLK") (pinfunction "SWCLK_SWCLK") (pintype "passive"))
      (node (ref "TP2") (pin "1") (pinfunction "1_1") (pintype "passive"))
    )
    (net (code "32") (name "Net-(IC2-PB3{slash}SWO)") (class "Default")
      (node (ref "IC2") (pin "89") (pinfunction "PB3/SWO_89") (pintype "bidirectional"))
      (node (ref "K5") (pin "SWO") (pinfunction "SWO_SWO") (pintype "passive"))
      (node (ref "TP8") (pin "1") (pinfunction "1_1") (pintype "passive"))
    )
    (net (code "33") (name "Net-(IC2-PB6)") (class "Default")
      (node (ref "IC2") (pin "92") (pinfunction "PB6_92") (pintype "bidirectional"))
      (node (ref "K6") (pin "2") (pinfunction "SCL_2") (pintype "bidirectional"))
      (node (ref "R15") (pin "P$1") (pinfunction "1_P$1") (pintype "passive"))
    )
    (net (code "34") (name "Net-(IC2-PB7)") (class "Default")
      (node (ref "IC2") (pin "93") (pinfunction "PB7_93") (pintype "bidirectional"))
      (node (ref "K6") (pin "3") (pinfunction "SDA_3") (pintype "bidirectional"))
      (node (ref "R16") (pin "P$1") (pinfunction "1_P$1") (pintype "passive"))
    )
    (net (code "35") (name "Net-(IC2-PC8)") (class "Default")
      (node (ref "IC2") (pin "65") (pinfunction "PC8_65") (pintype "bidirectional"))
      (node (ref "K3") (pin "7") (pinfunction "DAT0_7") (pintype "bidirectional"))
      (node (ref "R23") (pin "P$1") (pinfunction "1_P$1") (pintype "passive"))
    )
    (net (code "36") (name "Net-(IC2-PC9)") (class "Default")
      (node (ref "IC2") (pin "66") (pinfunction "PC9_66") (pintype "bidirectional"))
      (node (ref "K3") (pin "8") (pinfunction "DAT1_8") (pintype "bidirectional"))
      (node (ref "R18") (pin "P$1") (pinfunction "1_P$1") (pintype "passive"))
    )
    (net (code "37") (name "Net-(IC2-PC10)") (class "Default")
      (node (ref "IC2") (pin "78") (pinfunction "PC10_78") (pintype "bidirectional"))
      (node (ref "K3") (pin "1") (pinfunction "DAT2_1") (pintype "bidirectional"))
      (node (ref "R19") (pin "P$1") (pinfunction "1_P$1") (pintype "passive"))
    )
    (net (code "38") (name "Net-(IC2-PC11)") (class "Default")
      (node (ref "IC2") (pin "79") (pinfunction "PC11_79") (pintype "bidirectional"))
      (node (ref "K3") (pin "2") (pinfunction "CD/DAT3_2") (pintype "bidirectional"))
      (node (ref "R20") (pin "P$1") (pinfunction "1_P$1") (pintype "passive"))
    )
    (net (code "39") (name "Net-(IC2-PC12)") (class "Default")
      (node (ref "IC2") (pin "80") (pinfunction "PC12_80") (pintype "bidirectional"))
      (node (ref "K3") (pin "5") (pinfunction "CLK_5") (pintype "bidirectional"))
      (node (ref "R22") (pin "P$1") (pinfunction "1_P$1") (pintype "passive"))
    )
    (net (code "40") (name "Net-(IC2-PC13)") (class "Default")
      (node (ref "IC2") (pin "7") (pinfunction "PC13_7") (pintype "bidirectional"))
      (node (ref "K3") (pin "CD") (pinfunction "CD_CD") (pintype "bidirectional"))
    )
    (net (code "41") (name "Net-(IC2-PC14)") (class "Default")
      (node (ref "IC2") (pin "8") (pinfunction "PC14_8") (pintype "bidirectional"))
      (node (ref "K4") (pin "2") (pinfunction "~{RESET}_2") (pintype "bidirectional"))
    )
    (net (code "42") (name "Net-(IC2-PD0)") (class "Default")
      (node (ref "IC2") (pin "81") (pinfunction "PD0_81") (pintype "bidirectional"))
      (node (ref "K4") (pin "10") (pinfunction "DB2_10") (pintype "bidirectional"))
    )
    (net (code "43") (name "Net-(IC2-PD1)") (class "Default")
      (node (ref "IC2") (pin "82") (pinfunction "PD1_82") (pintype "bidirectional"))
      (node (ref "K4") (pin "9") (pinfunction "DB3_9") (pintype "bidirectional"))
    )
    (net (code "44") (name "Net-(IC2-PD2)") (class "Default")
      (node (ref "IC2") (pin "83") (pinfunction "PD2_83") (pintype "bidirectional"))
      (node (ref "K3") (pin "3") (pinfunction "CMD_3") (pintype "bidirectional"))
      (node (ref "R21") (pin "P$1") (pinfunction "1_P$1") (pintype "passive"))
    )
    (net (code "45") (name "Net-(IC2-PD4)") (class "Default")
      (node (ref "IC2") (pin "85") (pinfunction "PD4_85") (pintype "bidirectional"))
      (node (ref "K4") (pin "14") (pinfunction "~{RD}_14") (pintype "bidirectional"))
    )
    (net (code "46") (name "Net-(IC2-PD5)") (class "Default")
      (node (ref "IC2") (pin "86") (pinfunction "PD5_86") (pintype "bidirectional"))
      (node (ref "K4") (pin "15") (pinfunction "~{WR}_15") (pintype "bidirectional"))
    )
    (net (code "47") (name "Net-(IC2-PD7)") (class "Default")
      (node (ref "IC2") (pin "88") (pinfunction "PD7_88") (pintype "bidirectional"))
      (node (ref "K4") (pin "17") (pinfunction "~{CS}_17") (pintype "bidirectional"))
    )
    (net (code "48") (name "Net-(IC2-PD11)") (class "Default")
      (node (ref "IC2") (pin "58") (pinfunction "PD11_58") (pintype "bidirectional"))
      (node (ref "K4") (pin "16") (pinfunction "RS_16") (pintype "bidirectional"))
    )
    (net (code "49") (name "Net-(IC2-PD12)") (class "Default")
      (node (ref "IC2") (pin "59") (pinfunction "PD12_59") (pintype "bidirectional"))
      (node (ref "K4") (pin "19") (pinfunction "FMARK_19") (pintype "bidirectional"))
    )
    (net (code "50") (name "Net-(IC2-PD14)") (class "Default")
      (node (ref "IC2") (pin "61") (pinfunction "PD14_61") (pintype "bidirectional"))
      (node (ref "K4") (pin "12") (pinfunction "DB0_12") (pintype "bidirectional"))
    )
    (net (code "51") (name "Net-(IC2-PD15)") (class "Default")
      (node (ref "IC2") (pin "62") (pinfunction "PD15_62") (pintype "bidirectional"))
      (node (ref "K4") (pin "11") (pinfunction "DB1_11") (pintype "bidirectional"))
    )
    (net (code "52") (name "Net-(IC2-PE7)") (class "Default")
      (node (ref "IC2") (pin "38") (pinfunction "PE7_38") (pintype "bidirectional"))
      (node (ref "K4") (pin "8") (pinfunction "DB4_8") (pintype "bidirectional"))
    )
    (net (code "53") (name "Net-(IC2-PE8)") (class "Default")
      (node (ref "IC2") (pin "39") (pinfunction "PE8_39") (pintype "bidirectional"))
      (node (ref "K4") (pin "7") (pinfunction "DB5_7") (pintype "bidirectional"))
    )
    (net (code "54") (name "Net-(IC2-PE9)") (class "Default")
      (node (ref "IC2") (pin "40") (pinfunction "PE9_40") (pintype "bidirectional"))
      (node (ref "K4") (pin "6") (pinfunction "DB6_6") (pintype "bidirectional"))
    )
    (net (code "55") (name "Net-(IC2-PE10)") (class "Default")
      (node (ref "IC2") (pin "41") (pinfunction "PE10_41") (pintype "bidirectional"))
      (node (ref "K4") (pin "5") (pinfunction "DB7_5") (pintype "bidirectional"))
    )
    (net (code "56") (name "Net-(IC2-PE11)") (class "Default")
      (node (ref "IC2") (pin "42") (pinfunction "PE11_42") (pintype "bidirectional"))
      (node (ref "K4") (pin "4") (pinfunction "DB8_4") (pintype "bidirectional"))
    )
    (net (code "57") (name "Net-(IC2-VCAP_1)") (class "Default")
      (node (ref "C13") (pin "2") (pinfunction "2_2") (pintype "passive"))
      (node (ref "IC2") (pin "49") (pinfunction "VCAP_1_49") (pintype "power_in"))
    )
    (net (code "58") (name "Net-(IC2-VCAP_2)") (class "Default")
      (node (ref "C12") (pin "2") (pinfunction "2_2") (pintype "passive"))
      (node (ref "IC2") (pin "73") (pinfunction "VCAP_2_73") (pintype "power_in"))
    )
    (net (code "59") (name "Net-(IC5-CTRL)") (class "Default")
      (node (ref "IC5") (pin "5") (pinfunction "CTRL_5") (pintype "input"))
      (node (ref "R10") (pin "P$2") (pinfunction "2_P$2") (pintype "passive"))
      (node (ref "R9") (pin "P$2") (pinfunction "2_P$2") (pintype "passive"))
      (node (ref "TP6") (pin "1") (pinfunction "1_1") (pintype "passive"))
    )
    (net (code "60") (name "Net-(IC5-FB)") (class "Default")
      (node (ref "IC5") (pin "2") (pinfunction "RS_2") (pintype "passive"))
      (node (ref "IC5") (pin "4") (pinfunction "FB_4") (pintype "power_in"))
      (node (ref "R14") (pin "P$2") (pinfunction "2_P$2") (pintype "passive"))
    )
    (net (code "61") (name "Net-(IC5-OVP)") (class "Default")
      (node (ref "IC5") (pin "7") (pinfunction "OVP_7") (pintype "input"))
      (node (ref "R25") (pin "P$2") (pinfunction "2_P$2") (pintype "passive"))
      (node (ref "R26") (pin "P$1") (pinfunction "1_P$1") (pintype "passive"))
    )
    (net (code "62") (name "Net-(K6-EINT)") (class "Default")
      (node (ref "K6") (pin "4") (pinfunction "EINT_4") (pintype "bidirectional"))
      (node (ref "R13") (pin "P$1") (pinfunction "1_P$1") (pintype "passive"))
    )
    (net (code "63") (name "PWM") (class "Default")
      (node (ref "IC2") (pin "32") (pinfunction "PA7/SPI1_MOSI_32") (pintype "bidirectional"))
      (node (ref "R10") (pin "P$1") (pinfunction "1_P$1") (pintype "passive"))
    )
    (net (code "64") (name "REST") (class "Default")
      (node (ref "IC2") (pin "34") (pinfunction "PC5_34") (pintype "bidirectional"))
      (node (ref "K6") (pin "5") (pinfunction "REST_5") (pintype "bidirectional"))
      (node (ref "R12") (pin "P$2") (pinfunction "2_P$2") (pintype "passive"))
    )
    (net (code "65") (name "SBU1") (class "Default")
      (node (ref "D2") (pin "2") (pinfunction "2_2") (pintype "passive"))
      (node (ref "IC2") (pin "25") (pinfunction "PA2_25") (pintype "bidirectional"))
      (node (ref "K1") (pin "A8") (pinfunction "SBU1_A8") (pintype "passive"))
      (node (ref "TP10") (pin "1") (pinfunction "1_1") (pintype "passive"))
    )
    (net (code "66") (name "SBU2") (class "Default")
      (node (ref "D4") (pin "2") (pinfunction "2_2") (pintype "passive"))
      (node (ref "IC2") (pin "26") (pinfunction "PA3_26") (pintype "bidirectional"))
      (node (ref "K1") (pin "B8") (pinfunction "SBU2_B8") (pintype "passive"))
      (node (ref "TP11") (pin "1") (pinfunction "1_1") (pintype "passive"))
    )
    (net (code "67") (name "SD_ON") (class "Default")
      (node (ref "IC2") (pin "15") (pinfunction "PC0_15") (pintype "bidirectional"))
      (node (ref "R3") (pin "P$1") (pinfunction "1_P$1") (pintype "passive"))
    )
    (net (code "68") (name "TOUCH_ON") (class "Default")
      (node (ref "IC2") (pin "47") (pinfunction "PB10_47") (pintype "bidirectional"))
      (node (ref "R24") (pin "P$2") (pinfunction "2_P$2") (pintype "passive"))
    )
    (net (code "69") (name "VBUS") (class "Default")
      (node (ref "D1") (pin "A") (pinfunction "1_A") (pintype "passive"))
      (node (ref "D3") (pin "4") (pinfunction "VCC_4") (pintype "passive"))
      (node (ref "K1") (pin "A4") (pinfunction "VBUS_A4") (pintype "passive"))
      (node (ref "K1") (pin "A9") (pinfunction "VBUS_A9") (pintype "passive"))
      (node (ref "K1") (pin "B4") (pinfunction "VBUS_B4") (pintype "passive"))
      (node (ref "K1") (pin "B9") (pinfunction "VBUS_B9") (pintype "passive"))
    )
    (net (code "70") (name "VCC") (class "Default")
      (node (ref "C14") (pin "1") (pinfunction "1_1") (pintype "passive"))
      (node (ref "C16") (pin "P$2") (pinfunction "2_P$2") (pintype "passive"))
      (node (ref "C4") (pin "2") (pinfunction "2_2") (pintype "passive"))
      (node (ref "IC5") (pin "3") (pinfunction "VIN_3") (pintype "input"))
      (node (ref "IC6") (pin "1") (pinfunction "CE_1") (pintype "passive"))
      (node (ref "IC6") (pin "4") (pinfunction "IN_4") (pintype "passive"))
      (node (ref "L1") (pin "1") (pinfunction "1_1") (pintype "passive"))
      (node (ref "R1") (pin "P$2") (pinfunction "2_P$2") (pintype "passive"))
      (node (ref "R8") (pin "1") (pinfunction "1_1") (pintype "passive"))
      (node (ref "TP5") (pin "1") (pinfunction "1_1") (pintype "passive"))
    )
    (net (code "71") (name "VDD") (class "Default")
      (node (ref "C19") (pin "2") (pinfunction "2_2") (pintype "passive"))
      (node (ref "C24") (pin "P$2") (pinfunction "2_P$2") (pintype "passive"))
      (node (ref "C49") (pin "P$2") (pinfunction "2_P$2") (pintype "passive"))
      (node (ref "K6") (pin "1") (pinfunction "VDD_1") (pintype "power_in"))
      (node (ref "L3") (pin "2") (pinfunction "2_2") (pintype "passive"))
      (node (ref "R12") (pin "P$1") (pinfunction "1_P$1") (pintype "passive"))
      (node (ref "R15") (pin "P$2") (pinfunction "2_P$2") (pintype "passive"))
      (node (ref "R16") (pin "P$2") (pinfunction "2_P$2") (pintype "passive"))
      (node (ref "TP16") (pin "1") (pinfunction "1_1") (pintype "passive"))
    )
    (net (code "72") (name "unconnected-(IC2-PA0-WKUP-Pad23)") (class "Default")
      (node (ref "IC2") (pin "23") (pinfunction "PA0-WKUP_23") (pintype "bidirectional"))
    )
    (net (code "73") (name "unconnected-(IC2-PA1-Pad24)") (class "Default")
      (node (ref "IC2") (pin "24") (pinfunction "PA1_24") (pintype "bidirectional"))
    )
    (net (code "74") (name "unconnected-(IC2-PA4{slash}SPI1_NSS{slash}OTG_HS_SOF-Pad29)") (class "Default")
      (node (ref "IC2") (pin "29") (pinfunction "PA4/SPI1_NSS/OTG_HS_SOF_29") (pintype "bidirectional"))
    )
    (net (code "75") (name "unconnected-(IC2-PA5{slash}SPI1_SCK-Pad30)") (class "Default")
      (node (ref "IC2") (pin "30") (pinfunction "PA5/SPI1_SCK_30") (pintype "bidirectional"))
    )
    (net (code "76") (name "unconnected-(IC2-PA6{slash}SPI1_MISO-Pad31)") (class "Default")
      (node (ref "IC2") (pin "31") (pinfunction "PA6/SPI1_MISO_31") (pintype "bidirectional"))
    )
    (net (code "77") (name "unconnected-(IC2-PA8{slash}OTG_FS_SOF-Pad67)") (class "Default")
      (node (ref "IC2") (pin "67") (pinfunction "PA8/OTG_FS_SOF_67") (pintype "bidirectional"))
    )
    (net (code "78") (name "unconnected-(IC2-PA9{slash}OTG_FS_VBUS-Pad68)") (class "Default")
      (node (ref "IC2") (pin "68") (pinfunction "PA9/OTG_FS_VBUS_68") (pintype "bidirectional"))
    )
    (net (code "79") (name "unconnected-(IC2-PA10{slash}OFG_FS_ID-Pad69)") (class "Default")
      (node (ref "IC2") (pin "69") (pinfunction "PA10/OFG_FS_ID_69") (pintype "bidirectional"))
    )
    (net (code "80") (name "unconnected-(IC2-PA11{slash}OTG_FS_DM-Pad70)") (class "Default")
      (node (ref "IC2") (pin "70") (pinfunction "PA11/OTG_FS_DM_70") (pintype "bidirectional"))
    )
    (net (code "81") (name "unconnected-(IC2-PA12{slash}OTG_FS_DP-Pad71)") (class "Default")
      (node (ref "IC2") (pin "71") (pinfunction "PA12/OTG_FS_DP_71") (pintype "bidirectional"))
    )
    (net (code "82") (name "unconnected-(IC2-PA15-Pad77)") (class "Default")
      (node (ref "IC2") (pin "77") (pinfunction "PA15_77") (pintype "bidirectional"))
    )
    (net (code "83") (name "unconnected-(IC2-PB0-Pad35)") (class "Default")
      (node (ref "IC2") (pin "35") (pinfunction "PB0_35") (pintype "bidirectional"))
    )
    (net (code "84") (name "unconnected-(IC2-PB1-Pad36)") (class "Default")
      (node (ref "IC2") (pin "36") (pinfunction "PB1_36") (pintype "bidirectional"))
    )
    (net (code "85") (name "unconnected-(IC2-PB2-Pad37)") (class "Default")
      (node (ref "IC2") (pin "37") (pinfunction "PB2_37") (pintype "bidirectional"))
    )
    (net (code "86") (name "unconnected-(IC2-PB4-Pad90)") (class "Default")
      (node (ref "IC2") (pin "90") (pinfunction "PB4_90") (pintype "bidirectional"))
    )
    (net (code "87") (name "unconnected-(IC2-PB5-Pad91)") (class "Default")
      (node (ref "IC2") (pin "91") (pinfunction "PB5_91") (pintype "bidirectional"))
    )
    (net (code "88") (name "unconnected-(IC2-PB8-Pad95)") (class "Default")
      (node (ref "IC2") (pin "95") (pinfunction "PB8_95") (pintype "bidirectional"))
    )
    (net (code "89") (name "unconnected-(IC2-PB9-Pad96)") (class "Default")
      (node (ref "IC2") (pin "96") (pinfunction "PB9_96") (pintype "bidirectional"))
    )
    (net (code "90") (name "unconnected-(IC2-PB11-Pad48)") (class "Default")
      (node (ref "IC2") (pin "48") (pinfunction "PB11_48") (pintype "bidirectional"))
    )
    (net (code "91") (name "unconnected-(IC2-PB12{slash}OTG_HS_ID-Pad51)") (class "Default")
      (node (ref "IC2") (pin "51") (pinfunction "PB12/OTG_HS_ID_51") (pintype "bidirectional"))
    )
    (net (code "92") (name "unconnected-(IC2-PC1-Pad16)") (class "Default")
      (node (ref "IC2") (pin "16") (pinfunction "PC1_16") (pintype "bidirectional"))
    )
    (net (code "93") (name "unconnected-(IC2-PC2-Pad17)") (class "Default")
      (node (ref "IC2") (pin "17") (pinfunction "PC2_17") (pintype "bidirectional"))
    )
    (net (code "94") (name "unconnected-(IC2-PC3-Pad18)") (class "Default")
      (node (ref "IC2") (pin "18") (pinfunction "PC3_18") (pintype "bidirectional"))
    )
    (net (code "95") (name "unconnected-(IC2-PC6-Pad63)") (class "Default")
      (node (ref "IC2") (pin "63") (pinfunction "PC6_63") (pintype "bidirectional"))
    )
    (net (code "96") (name "unconnected-(IC2-PC7-Pad64)") (class "Default")
      (node (ref "IC2") (pin "64") (pinfunction "PC7_64") (pintype "bidirectional"))
    )
    (net (code "97") (name "unconnected-(IC2-PC15-Pad9)") (class "Default")
      (node (ref "IC2") (pin "9") (pinfunction "PC15_9") (pintype "bidirectional"))
    )
    (net (code "98") (name "unconnected-(IC2-PD3-Pad84)") (class "Default")
      (node (ref "IC2") (pin "84") (pinfunction "PD3_84") (pintype "bidirectional"))
    )
    (net (code "99") (name "unconnected-(IC2-PD6-Pad87)") (class "Default")
      (node (ref "IC2") (pin "87") (pinfunction "PD6_87") (pintype "bidirectional"))
    )
    (net (code "100") (name "unconnected-(IC2-PD8-Pad55)") (class "Default")
      (node (ref "IC2") (pin "55") (pinfunction "PD8_55") (pintype "bidirectional"))
    )
    (net (code "101") (name "unconnected-(IC2-PD9-Pad56)") (class "Default")
      (node (ref "IC2") (pin "56") (pinfunction "PD9_56") (pintype "bidirectional"))
    )
    (net (code "102") (name "unconnected-(IC2-PD10-Pad57)") (class "Default")
      (node (ref "IC2") (pin "57") (pinfunction "PD10_57") (pintype "bidirectional"))
    )
    (net (code "103") (name "unconnected-(IC2-PD13-Pad60)") (class "Default")
      (node (ref "IC2") (pin "60") (pinfunction "PD13_60") (pintype "bidirectional"))
    )
    (net (code "104") (name "unconnected-(IC2-PE0-Pad97)") (class "Default")
      (node (ref "IC2") (pin "97") (pinfunction "PE0_97") (pintype "bidirectional"))
    )
    (net (code "105") (name "unconnected-(IC2-PE1-Pad98)") (class "Default")
      (node (ref "IC2") (pin "98") (pinfunction "PE1_98") (pintype "bidirectional"))
    )
    (net (code "106") (name "unconnected-(IC2-PE2-Pad1)") (class "Default")
      (node (ref "IC2") (pin "1") (pinfunction "PE2_1") (pintype "bidirectional"))
    )
    (net (code "107") (name "unconnected-(IC2-PE3-Pad2)") (class "Default")
      (node (ref "IC2") (pin "2") (pinfunction "PE3_2") (pintype "bidirectional"))
    )
    (net (code "108") (name "unconnected-(IC2-PE4-Pad3)") (class "Default")
      (node (ref "IC2") (pin "3") (pinfunction "PE4_3") (pintype "bidirectional"))
    )
    (net (code "109") (name "unconnected-(IC2-PE5-Pad4)") (class "Default")
      (node (ref "IC2") (pin "4") (pinfunction "PE5_4") (pintype "bidirectional"))
    )
    (net (code "110") (name "unconnected-(IC2-PE6-Pad5)") (class "Default")
      (node (ref "IC2") (pin "5") (pinfunction "PE6_5") (pintype "bidirectional"))
    )
    (net (code "111") (name "unconnected-(IC2-PE12-Pad43)") (class "Default")
      (node (ref "IC2") (pin "43") (pinfunction "PE12_43") (pintype "bidirectional"))
    )
    (net (code "112") (name "unconnected-(IC2-PE13-Pad44)") (class "Default")
      (node (ref "IC2") (pin "44") (pinfunction "PE13_44") (pintype "bidirectional"))
    )
    (net (code "113") (name "unconnected-(IC2-PE14-Pad45)") (class "Default")
      (node (ref "IC2") (pin "45") (pinfunction "PE14_45") (pintype "bidirectional"))
    )
    (net (code "114") (name "unconnected-(IC2-PE15-Pad46)") (class "Default")
      (node (ref "IC2") (pin "46") (pinfunction "PE15_46") (pintype "bidirectional"))
    )
    (net (code "115") (name "unconnected-(IC6-NC-Pad3)") (class "Default")
      (node (ref "IC6") (pin "3") (pinfunction "NC_3") (pintype "passive"))
    )
    (net (code "116") (name "unconnected-(K1-RX1+-PadB11)") (class "Default")
      (node (ref "K1") (pin "B11") (pinfunction "RX1+_B11") (pintype "passive"))
    )
    (net (code "117") (name "unconnected-(K1-RX1--PadB10)") (class "Default")
      (node (ref "K1") (pin "B10") (pinfunction "RX1-_B10") (pintype "passive"))
    )
    (net (code "118") (name "unconnected-(K1-RX2+-PadA11)") (class "Default")
      (node (ref "K1") (pin "A11") (pinfunction "RX2+_A11") (pintype "passive"))
    )
    (net (code "119") (name "unconnected-(K1-RX2--PadA10)") (class "Default")
      (node (ref "K1") (pin "A10") (pinfunction "RX2-_A10") (pintype "passive"))
    )
    (net (code "120") (name "unconnected-(K1-TX1+-PadA2)") (class "Default")
      (node (ref "K1") (pin "A2") (pinfunction "TX1+_A2") (pintype "passive"))
    )
    (net (code "121") (name "unconnected-(K1-TX1--PadA3)") (class "Default")
      (node (ref "K1") (pin "A3") (pinfunction "TX1-_A3") (pintype "passive"))
    )
    (net (code "122") (name "unconnected-(K1-TX2+-PadB2)") (class "Default")
      (node (ref "K1") (pin "B2") (pinfunction "TX2+_B2") (pintype "passive"))
    )
    (net (code "123") (name "unconnected-(K1-TX2--PadB3)") (class "Default")
      (node (ref "K1") (pin "B3") (pinfunction "TX2-_B3") (pintype "passive"))
    )
    (net (code "124") (name "unconnected-(K6-NC-Pad8)") (class "Default")
      (node (ref "K6") (pin "8") (pinfunction "NC_8") (pintype "passive"))
    )
  )
)
